# Pfeiffer_Compact_Gauge_Controller.net
KiCad netlist of a schematic drawn in EAGLE
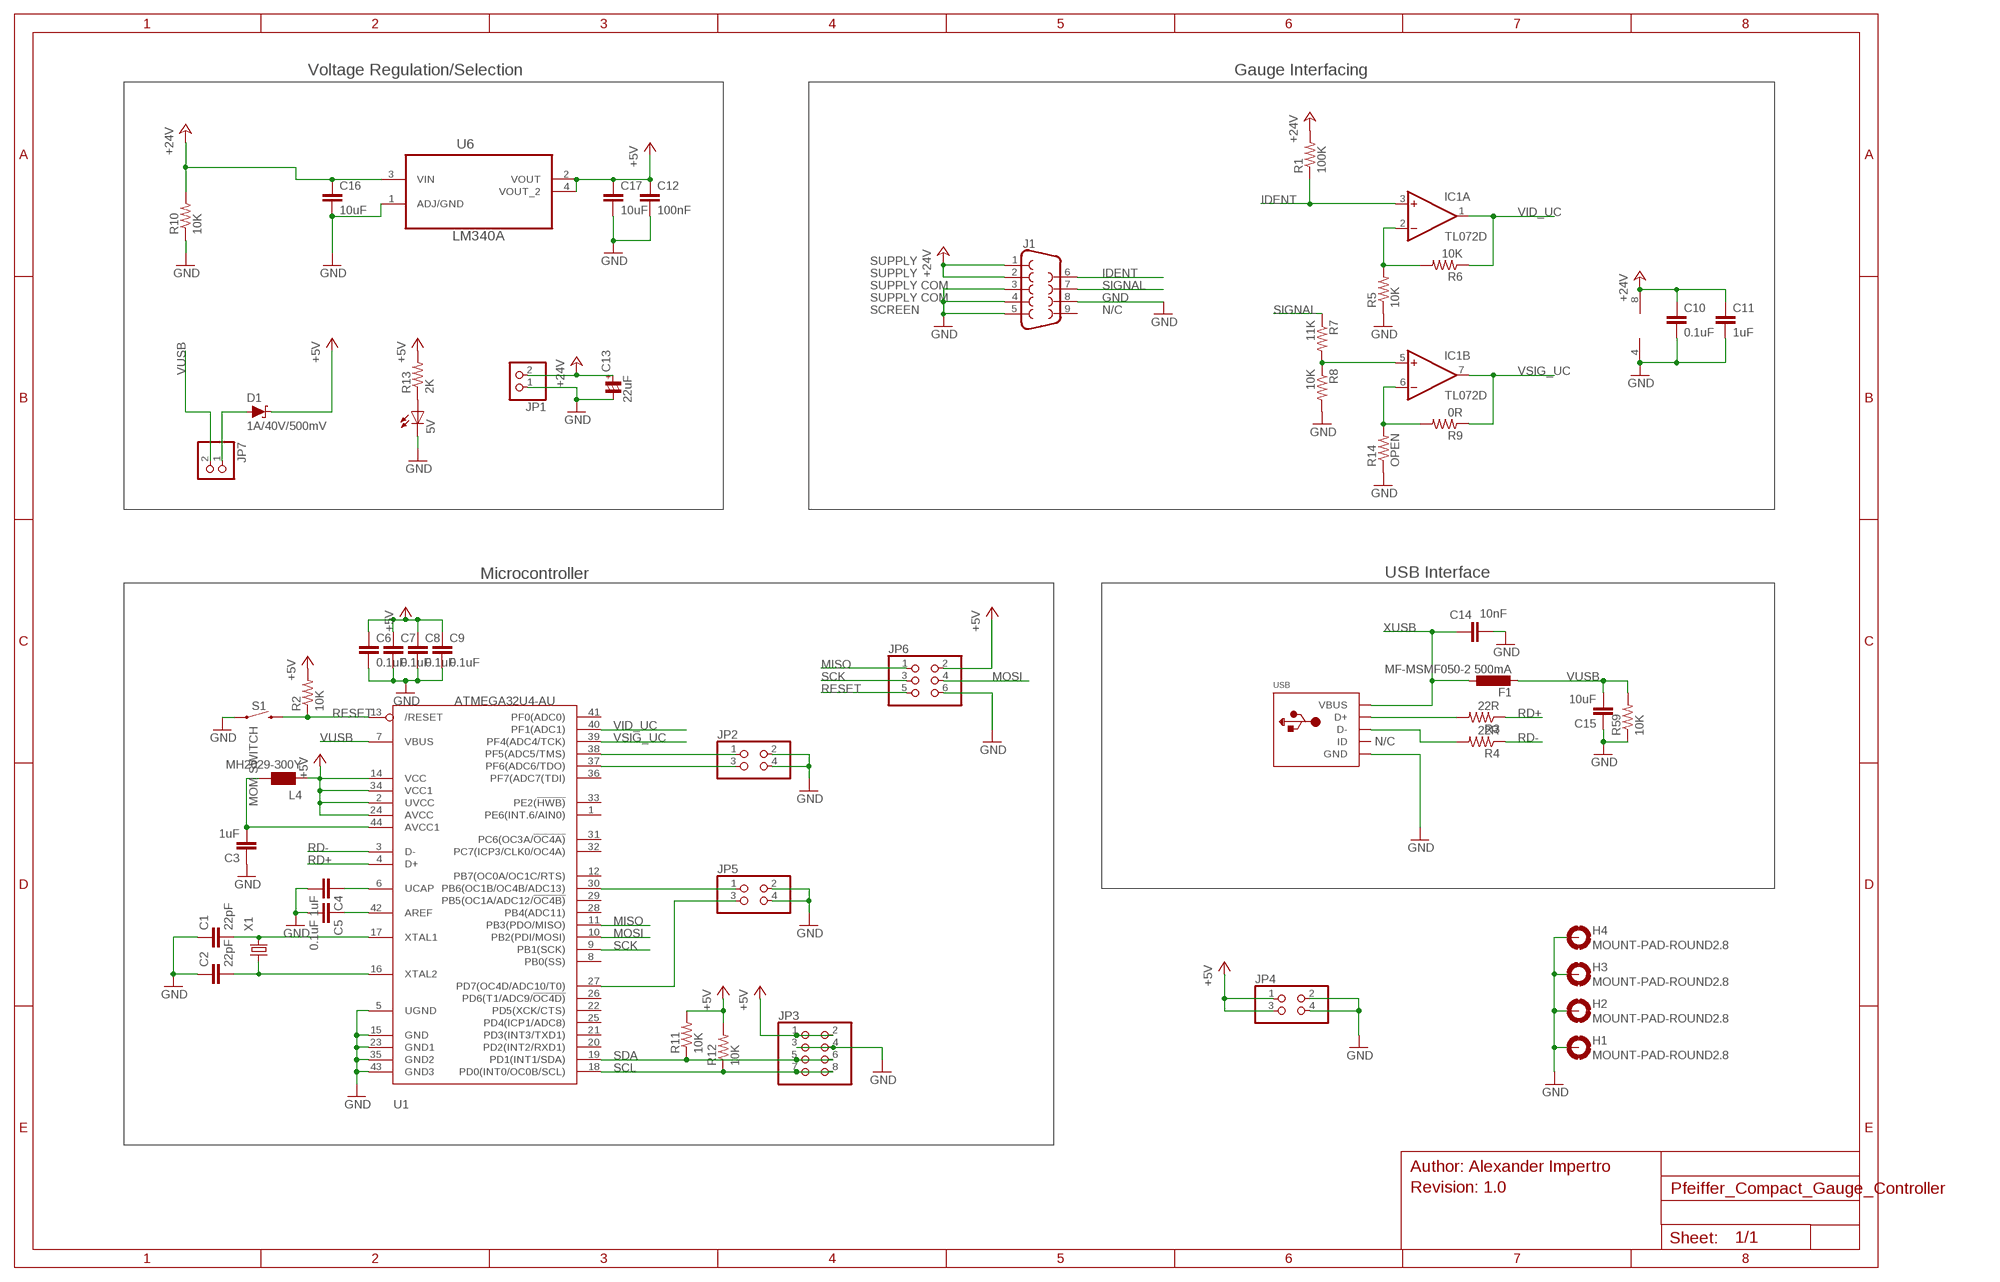
[diagram p0: schematic, sheet 1]

(export (version "E")
  (design (tool "Eeschema 10.0.6"))
  (components
    (comp (ref "5V")
      (value "LEDCHIPLED_0805")
      (footprint "eagle-import:CHIPLED_0805")
      (libsource (lib "eagle-import") (part "LEDCHIPLED_0805"))
    )
    (comp (ref "C1")
      (value "22pF")
      (footprint "eagle-import:C0805")
      (libsource (lib "eagle-import") (part "C-EUC0805"))
    )
    (comp (ref "C2")
      (value "22pF")
      (footprint "eagle-import:C0805")
      (libsource (lib "eagle-import") (part "C-EUC0805"))
    )
    (comp (ref "C3")
      (value "1uF")
      (footprint "eagle-import:C0805")
      (libsource (lib "eagle-import") (part "C-EUC0805"))
    )
    (comp (ref "C4")
      (value "1uF")
      (footprint "eagle-import:C0805")
      (libsource (lib "eagle-import") (part "C-EUC0805"))
    )
    (comp (ref "C5")
      (value "0.1uF")
      (footprint "eagle-import:C0805")
      (libsource (lib "eagle-import") (part "C-EUC0805"))
    )
    (comp (ref "C6")
      (value "0.1uF")
      (footprint "eagle-import:C0805")
      (libsource (lib "eagle-import") (part "C-EUC0805"))
    )
    (comp (ref "C7")
      (value "0.1uF")
      (footprint "eagle-import:C0805")
      (libsource (lib "eagle-import") (part "C-EUC0805"))
    )
    (comp (ref "C8")
      (value "0.1uF")
      (footprint "eagle-import:C0805")
      (libsource (lib "eagle-import") (part "C-EUC0805"))
    )
    (comp (ref "C9")
      (value "0.1uF")
      (footprint "eagle-import:C0805")
      (libsource (lib "eagle-import") (part "C-EUC0805"))
    )
    (comp (ref "C10")
      (value "0.1uF")
      (footprint "eagle-import:C0805")
      (libsource (lib "eagle-import") (part "C-EUC0805"))
    )
    (comp (ref "C11")
      (value "1uF")
      (footprint "eagle-import:C0805")
      (libsource (lib "eagle-import") (part "C-EUC0805"))
    )
    (comp (ref "C12")
      (value "100nF")
      (footprint "eagle-import:C0805")
      (libsource (lib "eagle-import") (part "C-EUC0805"))
    )
    (comp (ref "C13")
      (value "22uF")
      (footprint "eagle-import:CSV-C")
      (libsource (lib "eagle-import") (part "CP_SV-C"))
    )
    (comp (ref "C14")
      (value "10nF")
      (footprint "eagle-import:C0805")
      (libsource (lib "eagle-import") (part "C-EUC0805"))
    )
    (comp (ref "C15")
      (value "10uF")
      (footprint "eagle-import:C0805")
      (libsource (lib "eagle-import") (part "C-EUC0805"))
    )
    (comp (ref "C16")
      (value "10uF")
      (footprint "eagle-import:C0805")
      (libsource (lib "eagle-import") (part "C-EUC0805"))
    )
    (comp (ref "C17")
      (value "10uF")
      (footprint "eagle-import:C0805")
      (libsource (lib "eagle-import") (part "C-EUC0805"))
    )
    (comp (ref "D1")
      (value "1A/40V/500mV")
      (footprint "eagle-import:SMA-DIODE")
      (libsource (lib "eagle-import") (part "DIODE-SCHOTTKY-SS14"))
    )
    (comp (ref "F1")
      (value "MF-MSMF050-2 500mA")
      (footprint "eagle-import:PROTEZIONE_L1812")
      (fields (field (name "PART_NUMBER") "MF-MSMF050-2"))
      (libsource (lib "eagle-import") (part "PROTEZIONE_0002_MF-MSMF050-2"))
    )
    (comp (ref "H1")
      (value "MOUNT-PAD-ROUND2.8")
      (footprint "eagle-import:2,8-PAD")
      (libsource (lib "eagle-import") (part "MOUNT-PAD-ROUND2.8"))
    )
    (comp (ref "H2")
      (value "MOUNT-PAD-ROUND2.8")
      (footprint "eagle-import:2,8-PAD")
      (libsource (lib "eagle-import") (part "MOUNT-PAD-ROUND2.8"))
    )
    (comp (ref "H3")
      (value "MOUNT-PAD-ROUND2.8")
      (footprint "eagle-import:2,8-PAD")
      (libsource (lib "eagle-import") (part "MOUNT-PAD-ROUND2.8"))
    )
    (comp (ref "H4")
      (value "MOUNT-PAD-ROUND2.8")
      (footprint "eagle-import:2,8-PAD")
      (libsource (lib "eagle-import") (part "MOUNT-PAD-ROUND2.8"))
    )
    (comp (ref "IC1")
      (value "TL072D")
      (footprint "eagle-import:SO08")
      (libsource (lib "eagle-import") (part "TL072D"))
    )
    (comp (ref "J1")
      (value "DB9MALE")
      (footprint "eagle-import:DB9_MALE")
      (libsource (lib "eagle-import") (part "DB9MALE"))
    )
    (comp (ref "JP1")
      (value "PINHD-1X2/90")
      (footprint "eagle-import:1X02_90")
      (libsource (lib "eagle-import") (part "PINHD-1X2/90"))
    )
    (comp (ref "JP2")
      (value "PINHD-2X2")
      (footprint "eagle-import:2X02")
      (libsource (lib "eagle-import") (part "PINHD-2X2"))
    )
    (comp (ref "JP3")
      (value "PINHD-2X4")
      (footprint "eagle-import:2X04")
      (libsource (lib "eagle-import") (part "PINHD-2X4"))
    )
    (comp (ref "JP4")
      (value "PINHD-2X2")
      (footprint "eagle-import:2X02")
      (libsource (lib "eagle-import") (part "PINHD-2X2"))
    )
    (comp (ref "JP5")
      (value "PINHD-2X2")
      (footprint "eagle-import:2X02")
      (libsource (lib "eagle-import") (part "PINHD-2X2"))
    )
    (comp (ref "JP6")
      (value "PINHD-2X3")
      (footprint "eagle-import:2X03")
      (libsource (lib "eagle-import") (part "PINHD-2X3"))
    )
    (comp (ref "JP7")
      (value "PINHD-1X2")
      (footprint "eagle-import:1X02")
      (libsource (lib "eagle-import") (part "PINHD-1X2"))
    )
    (comp (ref "L4")
      (value "MH2029-300Y")
      (footprint "eagle-import:PROTEZIONE_0805")
      (fields (field (name "PART_NUMBER") "BLM21PG300SN1D_/_MH2029-300Y"))
      (libsource (lib "eagle-import") (part "PROTEZIONE_0001_BLM21PG300SN1D_/_MH2029-300Y"))
    )
    (comp (ref "R1")
      (value "100K")
      (footprint "eagle-import:R0805")
      (libsource (lib "eagle-import") (part "R-US_R0805"))
    )
    (comp (ref "R2")
      (value "10K")
      (footprint "eagle-import:R0805")
      (libsource (lib "eagle-import") (part "R-US_R0805"))
    )
    (comp (ref "R3")
      (value "22R")
      (footprint "eagle-import:R0805")
      (libsource (lib "eagle-import") (part "R-US_R0805"))
    )
    (comp (ref "R4")
      (value "22R")
      (footprint "eagle-import:R0805")
      (libsource (lib "eagle-import") (part "R-US_R0805"))
    )
    (comp (ref "R5")
      (value "10K")
      (footprint "eagle-import:R0805")
      (libsource (lib "eagle-import") (part "R-US_R0805"))
    )
    (comp (ref "R6")
      (value "10K")
      (footprint "eagle-import:R0805")
      (libsource (lib "eagle-import") (part "R-US_R0805"))
    )
    (comp (ref "R7")
      (value "11K")
      (footprint "eagle-import:R0805")
      (libsource (lib "eagle-import") (part "R-US_R0805"))
    )
    (comp (ref "R8")
      (value "10K")
      (footprint "eagle-import:R0805")
      (libsource (lib "eagle-import") (part "R-US_R0805"))
    )
    (comp (ref "R9")
      (value "0R")
      (footprint "eagle-import:R0805")
      (libsource (lib "eagle-import") (part "R-US_R0805"))
    )
    (comp (ref "R10")
      (value "10K")
      (footprint "eagle-import:R0805")
      (libsource (lib "eagle-import") (part "R-US_R0805"))
    )
    (comp (ref "R11")
      (value "10K")
      (footprint "eagle-import:R0805")
      (libsource (lib "eagle-import") (part "R-US_R0805"))
    )
    (comp (ref "R12")
      (value "10K")
      (footprint "eagle-import:R0805")
      (libsource (lib "eagle-import") (part "R-US_R0805"))
    )
    (comp (ref "R13")
      (value "2K")
      (footprint "eagle-import:R0805")
      (libsource (lib "eagle-import") (part "R-US_R0805"))
    )
    (comp (ref "R14")
      (value "OPEN")
      (footprint "eagle-import:R0805")
      (libsource (lib "eagle-import") (part "R-US_R0805"))
    )
    (comp (ref "R59")
      (value "10K")
      (footprint "eagle-import:R0805")
      (libsource (lib "eagle-import") (part "R-US_R0805"))
    )
    (comp (ref "S1")
      (value "MOM SWITCH")
      (footprint "eagle-import:TACTILE_SWITCH_SMD_5.2MM")
      (libsource (lib "eagle-import") (part "MOMENTARY-SWITCH-SPST-SMD-5.2MM"))
    )
    (comp (ref "U1")
      (value "ATMEGA32U4-AU")
      (footprint "eagle-import:TQFP44")
      (libsource (lib "eagle-import") (part "ATMEGA32U4-AU"))
    )
    (comp (ref "U6")
      (value "LM340A")
      (footprint "eagle-import:SOT230P696X180-4N")
      (fields (field (name "MPN") "LM1117IMP-5.0"))
      (libsource (lib "eagle-import") (part "LM1117IMP-5.0"))
    )
    (comp (ref "USB")
      (value "USBMINIB")
      (footprint "eagle-import:USB-MINIB")
      (libsource (lib "eagle-import") (part "USBMINIB"))
    )
    (comp (ref "X1")
      (value "KX-7")
      (footprint "eagle-import:3.2X2.5_KX-7")
      (libsource (lib "eagle-import") (part "KX-7"))
    )
  )
  (nets
    (net (code "1") (name "+5V") (class "Default")
      (node (ref "C12") (pin "1") (pinfunction "1_1") (pintype "passive"))
      (node (ref "C17") (pin "1") (pinfunction "1_1") (pintype "passive"))
      (node (ref "C6") (pin "1") (pinfunction "1_1") (pintype "passive"))
      (node (ref "C7") (pin "1") (pinfunction "1_1") (pintype "passive"))
      (node (ref "C8") (pin "1") (pinfunction "1_1") (pintype "passive"))
      (node (ref "C9") (pin "1") (pinfunction "1_1") (pintype "passive"))
      (node (ref "D1") (pin "C") (pinfunction "C_C") (pintype "passive"))
      (node (ref "JP3") (pin "1") (pinfunction "1_1") (pintype "passive"))
      (node (ref "JP3") (pin "2") (pinfunction "2_2") (pintype "passive"))
      (node (ref "JP4") (pin "1") (pinfunction "1_1") (pintype "passive"))
      (node (ref "JP4") (pin "3") (pinfunction "3_3") (pintype "passive"))
      (node (ref "JP6") (pin "2") (pinfunction "2_2") (pintype "passive"))
      (node (ref "L4") (pin "1") (pinfunction "1_1") (pintype "passive"))
      (node (ref "R11") (pin "2") (pinfunction "2_2") (pintype "passive"))
      (node (ref "R12") (pin "2") (pinfunction "2_2") (pintype "passive"))
      (node (ref "R13") (pin "2") (pinfunction "2_2") (pintype "passive"))
      (node (ref "R2") (pin "2") (pinfunction "2_2") (pintype "passive"))
      (node (ref "U1") (pin "14") (pinfunction "VCC_14") (pintype "bidirectional"))
      (node (ref "U1") (pin "2") (pinfunction "UVCC_2") (pintype "bidirectional"))
      (node (ref "U1") (pin "24") (pinfunction "AVCC_24") (pintype "bidirectional"))
      (node (ref "U1") (pin "34") (pinfunction "VCC1_34") (pintype "bidirectional"))
      (node (ref "U6") (pin "2") (pinfunction "VOUT_2") (pintype "output"))
      (node (ref "U6") (pin "4") (pinfunction "VOUT_2_4") (pintype "output"))
    )
    (net (code "2") (name "+24V") (class "Default")
      (node (ref "C10") (pin "1") (pinfunction "1_1") (pintype "passive"))
      (node (ref "C11") (pin "1") (pinfunction "1_1") (pintype "passive"))
      (node (ref "C13") (pin "+") (pinfunction "+_+") (pintype "passive"))
      (node (ref "C16") (pin "1") (pinfunction "1_1") (pintype "passive"))
      (node (ref "IC1") (pin "8") (pinfunction "V+_8") (pintype "power_in"))
      (node (ref "J1") (pin "1") (pinfunction "1_1") (pintype "passive"))
      (node (ref "J1") (pin "2") (pinfunction "2_2") (pintype "passive"))
      (node (ref "JP1") (pin "2") (pinfunction "2_2") (pintype "passive"))
      (node (ref "R1") (pin "2") (pinfunction "2_2") (pintype "passive"))
      (node (ref "R10") (pin "2") (pinfunction "2_2") (pintype "passive"))
      (node (ref "U6") (pin "3") (pinfunction "VIN_3") (pintype "input"))
    )
    (net (code "3") (name "/IDENT") (class "Default")
      (node (ref "IC1") (pin "3") (pinfunction "+IN_3") (pintype "input"))
      (node (ref "J1") (pin "6") (pinfunction "6_6") (pintype "passive"))
      (node (ref "R1") (pin "1") (pinfunction "1_1") (pintype "passive"))
    )
    (net (code "4") (name "/MISO") (class "Default")
      (node (ref "JP6") (pin "1") (pinfunction "1_1") (pintype "passive"))
      (node (ref "U1") (pin "11") (pinfunction "PB3(PDO/MISO)_11") (pintype "bidirectional"))
    )
    (net (code "5") (name "/MOSI") (class "Default")
      (node (ref "JP6") (pin "4") (pinfunction "4_4") (pintype "passive"))
      (node (ref "U1") (pin "10") (pinfunction "PB2(PDI/MOSI)_10") (pintype "bidirectional"))
    )
    (net (code "6") (name "/RD+") (class "Default")
      (node (ref "R3") (pin "1") (pinfunction "1_1") (pintype "passive"))
      (node (ref "U1") (pin "4") (pinfunction "D+_4") (pintype "bidirectional"))
    )
    (net (code "7") (name "/RD-") (class "Default")
      (node (ref "R4") (pin "1") (pinfunction "1_1") (pintype "passive"))
      (node (ref "U1") (pin "3") (pinfunction "D-_3") (pintype "bidirectional"))
    )
    (net (code "8") (name "/RESET") (class "Default")
      (node (ref "JP6") (pin "5") (pinfunction "5_5") (pintype "passive"))
      (node (ref "R2") (pin "1") (pinfunction "1_1") (pintype "passive"))
      (node (ref "S1") (pin "3") (pinfunction "2_3") (pintype "passive"))
      (node (ref "U1") (pin "13") (pinfunction "/RESET_13") (pintype "bidirectional"))
    )
    (net (code "9") (name "/SCK") (class "Default")
      (node (ref "JP6") (pin "3") (pinfunction "3_3") (pintype "passive"))
      (node (ref "U1") (pin "9") (pinfunction "PB1(SCK)_9") (pintype "bidirectional"))
    )
    (net (code "10") (name "/SCL") (class "Default")
      (node (ref "JP3") (pin "7") (pinfunction "7_7") (pintype "passive"))
      (node (ref "JP3") (pin "8") (pinfunction "8_8") (pintype "passive"))
      (node (ref "R12") (pin "1") (pinfunction "1_1") (pintype "passive"))
      (node (ref "U1") (pin "18") (pinfunction "PD0(INT0/OC0B/SCL)_18") (pintype "bidirectional"))
    )
    (net (code "11") (name "/SDA") (class "Default")
      (node (ref "JP3") (pin "5") (pinfunction "5_5") (pintype "passive"))
      (node (ref "JP3") (pin "6") (pinfunction "6_6") (pintype "passive"))
      (node (ref "R11") (pin "1") (pinfunction "1_1") (pintype "passive"))
      (node (ref "U1") (pin "19") (pinfunction "PD1(INT1/SDA)_19") (pintype "bidirectional"))
    )
    (net (code "12") (name "/SIGNAL") (class "Default")
      (node (ref "J1") (pin "7") (pinfunction "7_7") (pintype "passive"))
      (node (ref "R7") (pin "1") (pinfunction "1_1") (pintype "passive"))
    )
    (net (code "13") (name "/VID_UC") (class "Default")
      (node (ref "IC1") (pin "1") (pinfunction "OUT_1") (pintype "output"))
      (node (ref "R6") (pin "1") (pinfunction "1_1") (pintype "passive"))
      (node (ref "U1") (pin "40") (pinfunction "PF1(ADC1)_40") (pintype "bidirectional"))
    )
    (net (code "14") (name "/VSIG_UC") (class "Default")
      (node (ref "IC1") (pin "7") (pinfunction "OUT_7") (pintype "output"))
      (node (ref "R9") (pin "1") (pinfunction "1_1") (pintype "passive"))
      (node (ref "U1") (pin "39") (pinfunction "PF4(ADC4/TCK)_39") (pintype "bidirectional"))
    )
    (net (code "15") (name "/VUSB") (class "Default")
      (node (ref "C15") (pin "2") (pinfunction "2_2") (pintype "passive"))
      (node (ref "F1") (pin "2") (pinfunction "2_2") (pintype "passive"))
      (node (ref "JP7") (pin "2") (pinfunction "2_2") (pintype "passive"))
      (node (ref "R59") (pin "2") (pinfunction "2_2") (pintype "passive"))
      (node (ref "U1") (pin "7") (pinfunction "VBUS_7") (pintype "bidirectional"))
    )
    (net (code "16") (name "/XUSB") (class "Default")
      (node (ref "C14") (pin "1") (pinfunction "1_1") (pintype "passive"))
      (node (ref "F1") (pin "1") (pinfunction "1_1") (pintype "passive"))
      (node (ref "USB") (pin "VBUS") (pinfunction "VBUS_VBUS") (pintype "power_in"))
    )
    (net (code "17") (name "GND") (class "Default")
      (node (ref "5V") (pin "C") (pinfunction "C_C") (pintype "passive"))
      (node (ref "C1") (pin "1") (pinfunction "1_1") (pintype "passive"))
      (node (ref "C10") (pin "2") (pinfunction "2_2") (pintype "passive"))
      (node (ref "C11") (pin "2") (pinfunction "2_2") (pintype "passive"))
      (node (ref "C12") (pin "2") (pinfunction "2_2") (pintype "passive"))
      (node (ref "C13") (pin "-") (pinfunction "-_-") (pintype "passive"))
      (node (ref "C14") (pin "2") (pinfunction "2_2") (pintype "passive"))
      (node (ref "C15") (pin "1") (pinfunction "1_1") (pintype "passive"))
      (node (ref "C16") (pin "2") (pinfunction "2_2") (pintype "passive"))
      (node (ref "C17") (pin "2") (pinfunction "2_2") (pintype "passive"))
      (node (ref "C2") (pin "1") (pinfunction "1_1") (pintype "passive"))
      (node (ref "C3") (pin "1") (pinfunction "1_1") (pintype "passive"))
      (node (ref "C4") (pin "2") (pinfunction "2_2") (pintype "passive"))
      (node (ref "C5") (pin "2") (pinfunction "2_2") (pintype "passive"))
      (node (ref "C6") (pin "2") (pinfunction "2_2") (pintype "passive"))
      (node (ref "C7") (pin "2") (pinfunction "2_2") (pintype "passive"))
      (node (ref "C8") (pin "2") (pinfunction "2_2") (pintype "passive"))
      (node (ref "C9") (pin "2") (pinfunction "2_2") (pintype "passive"))
      (node (ref "H1") (pin "B2,8") (pinfunction "MOUNT_B2,8") (pintype "passive"))
      (node (ref "H2") (pin "B2,8") (pinfunction "MOUNT_B2,8") (pintype "passive"))
      (node (ref "H3") (pin "B2,8") (pinfunction "MOUNT_B2,8") (pintype "passive"))
      (node (ref "H4") (pin "B2,8") (pinfunction "MOUNT_B2,8") (pintype "passive"))
      (node (ref "IC1") (pin "4") (pinfunction "V-_4") (pintype "power_in"))
      (node (ref "J1") (pin "3") (pinfunction "3_3") (pintype "passive"))
      (node (ref "J1") (pin "4") (pinfunction "4_4") (pintype "passive"))
      (node (ref "J1") (pin "5") (pinfunction "5_5") (pintype "passive"))
      (node (ref "J1") (pin "8") (pinfunction "8_8") (pintype "passive"))
      (node (ref "JP1") (pin "1") (pinfunction "1_1") (pintype "passive"))
      (node (ref "JP2") (pin "2") (pinfunction "2_2") (pintype "passive"))
      (node (ref "JP2") (pin "4") (pinfunction "4_4") (pintype "passive"))
      (node (ref "JP3") (pin "3") (pinfunction "3_3") (pintype "passive"))
      (node (ref "JP3") (pin "4") (pinfunction "4_4") (pintype "passive"))
      (node (ref "JP4") (pin "2") (pinfunction "2_2") (pintype "passive"))
      (node (ref "JP4") (pin "4") (pinfunction "4_4") (pintype "passive"))
      (node (ref "JP5") (pin "2") (pinfunction "2_2") (pintype "passive"))
      (node (ref "JP5") (pin "4") (pinfunction "4_4") (pintype "passive"))
      (node (ref "JP6") (pin "6") (pinfunction "6_6") (pintype "passive"))
      (node (ref "R10") (pin "1") (pinfunction "1_1") (pintype "passive"))
      (node (ref "R14") (pin "1") (pinfunction "1_1") (pintype "passive"))
      (node (ref "R5") (pin "1") (pinfunction "1_1") (pintype "passive"))
      (node (ref "R59") (pin "1") (pinfunction "1_1") (pintype "passive"))
      (node (ref "R8") (pin "2") (pinfunction "2_2") (pintype "passive"))
      (node (ref "S1") (pin "1") (pinfunction "1_1") (pintype "passive"))
      (node (ref "U1") (pin "15") (pinfunction "GND_15") (pintype "bidirectional"))
      (node (ref "U1") (pin "23") (pinfunction "GND1_23") (pintype "bidirectional"))
      (node (ref "U1") (pin "35") (pinfunction "GND2_35") (pintype "bidirectional"))
      (node (ref "U1") (pin "43") (pinfunction "GND3_43") (pintype "bidirectional"))
      (node (ref "U1") (pin "5") (pinfunction "UGND_5") (pintype "bidirectional"))
      (node (ref "U6") (pin "1") (pinfunction "ADJ/GND_1") (pintype "passive"))
      (node (ref "USB") (pin "GND") (pinfunction "GND_GND") (pintype "power_in"))
    )
    (net (code "18") (name "Net-(5V-PadA)") (class "Default")
      (node (ref "5V") (pin "A") (pinfunction "A_A") (pintype "passive"))
      (node (ref "R13") (pin "1") (pinfunction "1_1") (pintype "passive"))
    )
    (net (code "19") (name "Net-(D1-PadA)") (class "Default")
      (node (ref "D1") (pin "A") (pinfunction "A_A") (pintype "passive"))
      (node (ref "JP7") (pin "1") (pinfunction "1_1") (pintype "passive"))
    )
    (net (code "20") (name "Net-(IC1A--IN)") (class "Default")
      (node (ref "IC1") (pin "2") (pinfunction "-IN_2") (pintype "input"))
      (node (ref "R5") (pin "2") (pinfunction "2_2") (pintype "passive"))
      (node (ref "R6") (pin "2") (pinfunction "2_2") (pintype "passive"))
    )
    (net (code "21") (name "Net-(IC1B-+IN)") (class "Default")
      (node (ref "IC1") (pin "5") (pinfunction "+IN_5") (pintype "input"))
      (node (ref "R7") (pin "2") (pinfunction "2_2") (pintype "passive"))
      (node (ref "R8") (pin "1") (pinfunction "1_1") (pintype "passive"))
    )
    (net (code "22") (name "Net-(IC1B--IN)") (class "Default")
      (node (ref "IC1") (pin "6") (pinfunction "-IN_6") (pintype "input"))
      (node (ref "R14") (pin "2") (pinfunction "2_2") (pintype "passive"))
      (node (ref "R9") (pin "2") (pinfunction "2_2") (pintype "passive"))
    )
    (net (code "23") (name "Net-(R3-Pad2)") (class "Default")
      (node (ref "R3") (pin "2") (pinfunction "2_2") (pintype "passive"))
      (node (ref "USB") (pin "D+") (pinfunction "D+_D+") (pintype "bidirectional"))
    )
    (net (code "24") (name "Net-(R4-Pad2)") (class "Default")
      (node (ref "R4") (pin "2") (pinfunction "2_2") (pintype "passive"))
      (node (ref "USB") (pin "D-") (pinfunction "D-_D-") (pintype "bidirectional"))
    )
    (net (code "25") (name "Net-(U1-AREF)") (class "Default")
      (node (ref "C5") (pin "1") (pinfunction "1_1") (pintype "passive"))
      (node (ref "U1") (pin "42") (pinfunction "AREF_42") (pintype "bidirectional"))
    )
    (net (code "26") (name "Net-(U1-AVCC1)") (class "Default")
      (node (ref "C3") (pin "2") (pinfunction "2_2") (pintype "passive"))
      (node (ref "L4") (pin "2") (pinfunction "2_2") (pintype "passive"))
      (node (ref "U1") (pin "44") (pinfunction "AVCC1_44") (pintype "bidirectional"))
    )
    (net (code "27") (name "Net-(U1-PB6(OC1B{slash}OC4B{slash}ADC13))") (class "Default")
      (node (ref "JP5") (pin "1") (pinfunction "1_1") (pintype "passive"))
      (node (ref "U1") (pin "30") (pinfunction "PB6(OC1B/OC4B/ADC13)_30") (pintype "bidirectional"))
    )
    (net (code "28") (name "Net-(U1-PD7(OC4D{slash}ADC10{slash}T0))") (class "Default")
      (node (ref "JP5") (pin "3") (pinfunction "3_3") (pintype "passive"))
      (node (ref "U1") (pin "27") (pinfunction "PD7(OC4D/ADC10/T0)_27") (pintype "bidirectional"))
    )
    (net (code "29") (name "Net-(U1-PF5(ADC5{slash}TMS))") (class "Default")
      (node (ref "JP2") (pin "1") (pinfunction "1_1") (pintype "passive"))
      (node (ref "U1") (pin "38") (pinfunction "PF5(ADC5/TMS)_38") (pintype "bidirectional"))
    )
    (net (code "30") (name "Net-(U1-PF6(ADC6{slash}TDO))") (class "Default")
      (node (ref "JP2") (pin "3") (pinfunction "3_3") (pintype "passive"))
      (node (ref "U1") (pin "37") (pinfunction "PF6(ADC6/TDO)_37") (pintype "bidirectional"))
    )
    (net (code "31") (name "Net-(U1-UCAP)") (class "Default")
      (node (ref "C4") (pin "1") (pinfunction "1_1") (pintype "passive"))
      (node (ref "U1") (pin "6") (pinfunction "UCAP_6") (pintype "bidirectional"))
    )
    (net (code "32") (name "Net-(U1-XTAL1)") (class "Default")
      (node (ref "C1") (pin "2") (pinfunction "2_2") (pintype "passive"))
      (node (ref "U1") (pin "17") (pinfunction "XTAL1_17") (pintype "bidirectional"))
      (node (ref "X1") (pin "3") (pinfunction "2_3") (pintype "passive"))
    )
    (net (code "33") (name "Net-(U1-XTAL2)") (class "Default")
      (node (ref "C2") (pin "2") (pinfunction "2_2") (pintype "passive"))
      (node (ref "U1") (pin "16") (pinfunction "XTAL2_16") (pintype "bidirectional"))
      (node (ref "X1") (pin "1") (pinfunction "1_1") (pintype "passive"))
    )
    (net (code "34") (name "unconnected-(J1-Pad9)") (class "Default")
      (node (ref "J1") (pin "9") (pinfunction "9_9") (pintype "passive"))
    )
    (net (code "35") (name "unconnected-(U1-PB0(SS)-Pad8)") (class "Default")
      (node (ref "U1") (pin "8") (pinfunction "PB0(SS)_8") (pintype "bidirectional"))
    )
    (net (code "36") (name "unconnected-(U1-PB4(ADC11)-Pad28)") (class "Default")
      (node (ref "U1") (pin "28") (pinfunction "PB4(ADC11)_28") (pintype "bidirectional"))
    )
    (net (code "37") (name "unconnected-(U1-PB5(OC1A{slash}ADC12{slash}~{OC4B})-Pad29)") (class "Default")
      (node (ref "U1") (pin "29") (pinfunction "PB5(OC1A/ADC12/~{OC4B})_29") (pintype "bidirectional"))
    )
    (net (code "38") (name "unconnected-(U1-PB7(OC0A{slash}OC1C{slash}RTS)-Pad12)") (class "Default")
      (node (ref "U1") (pin "12") (pinfunction "PB7(OC0A/OC1C/RTS)_12") (pintype "bidirectional"))
    )
    (net (code "39") (name "unconnected-(U1-PC6(OC3A{slash}~{OC4A})-Pad31)") (class "Default")
      (node (ref "U1") (pin "31") (pinfunction "PC6(OC3A/~{OC4A})_31") (pintype "bidirectional"))
    )
    (net (code "40") (name "unconnected-(U1-PC7(ICP3{slash}CLK0{slash}OC4A)-Pad32)") (class "Default")
      (node (ref "U1") (pin "32") (pinfunction "PC7(ICP3/CLK0/OC4A)_32") (pintype "bidirectional"))
    )
    (net (code "41") (name "unconnected-(U1-PD2(INT2{slash}RXD1)-Pad20)") (class "Default")
      (node (ref "U1") (pin "20") (pinfunction "PD2(INT2/RXD1)_20") (pintype "bidirectional"))
    )
    (net (code "42") (name "unconnected-(U1-PD3(INT3{slash}TXD1)-Pad21)") (class "Default")
      (node (ref "U1") (pin "21") (pinfunction "PD3(INT3/TXD1)_21") (pintype "bidirectional"))
    )
    (net (code "43") (name "unconnected-(U1-PD4(ICP1{slash}ADC8)-Pad25)") (class "Default")
      (node (ref "U1") (pin "25") (pinfunction "PD4(ICP1/ADC8)_25") (pintype "bidirectional"))
    )
    (net (code "44") (name "unconnected-(U1-PD5(XCK{slash}CTS)-Pad22)") (class "Default")
      (node (ref "U1") (pin "22") (pinfunction "PD5(XCK/CTS)_22") (pintype "bidirectional"))
    )
    (net (code "45") (name "unconnected-(U1-PD6(T1{slash}ADC9{slash}~{OC4D})-Pad26)") (class "Default")
      (node (ref "U1") (pin "26") (pinfunction "PD6(T1/ADC9/~{OC4D})_26") (pintype "bidirectional"))
    )
    (net (code "46") (name "unconnected-(U1-PE2(~{HWB})-Pad33)") (class "Default")
      (node (ref "U1") (pin "33") (pinfunction "PE2(~{HWB})_33") (pintype "bidirectional"))
    )
    (net (code "47") (name "unconnected-(U1-PE6(INT.6{slash}AIN0)-Pad1)") (class "Default")
      (node (ref "U1") (pin "1") (pinfunction "PE6(INT.6/AIN0)_1") (pintype "bidirectional"))
    )
    (net (code "48") (name "unconnected-(U1-PF0(ADC0)-Pad41)") (class "Default")
      (node (ref "U1") (pin "41") (pinfunction "PF0(ADC0)_41") (pintype "bidirectional"))
    )
    (net (code "49") (name "unconnected-(U1-PF7(ADC7(TDI)-Pad36)") (class "Default")
      (node (ref "U1") (pin "36") (pinfunction "PF7(ADC7(TDI)_36") (pintype "bidirectional"))
    )
    (net (code "50") (name "unconnected-(USB-PadID)") (class "Default")
      (node (ref "USB") (pin "ID") (pinfunction "ID_ID") (pintype "bidirectional"))
    )
  )
)
